# CAP_Group.net
KiCad netlist of a schematic drawn in Altium Designer
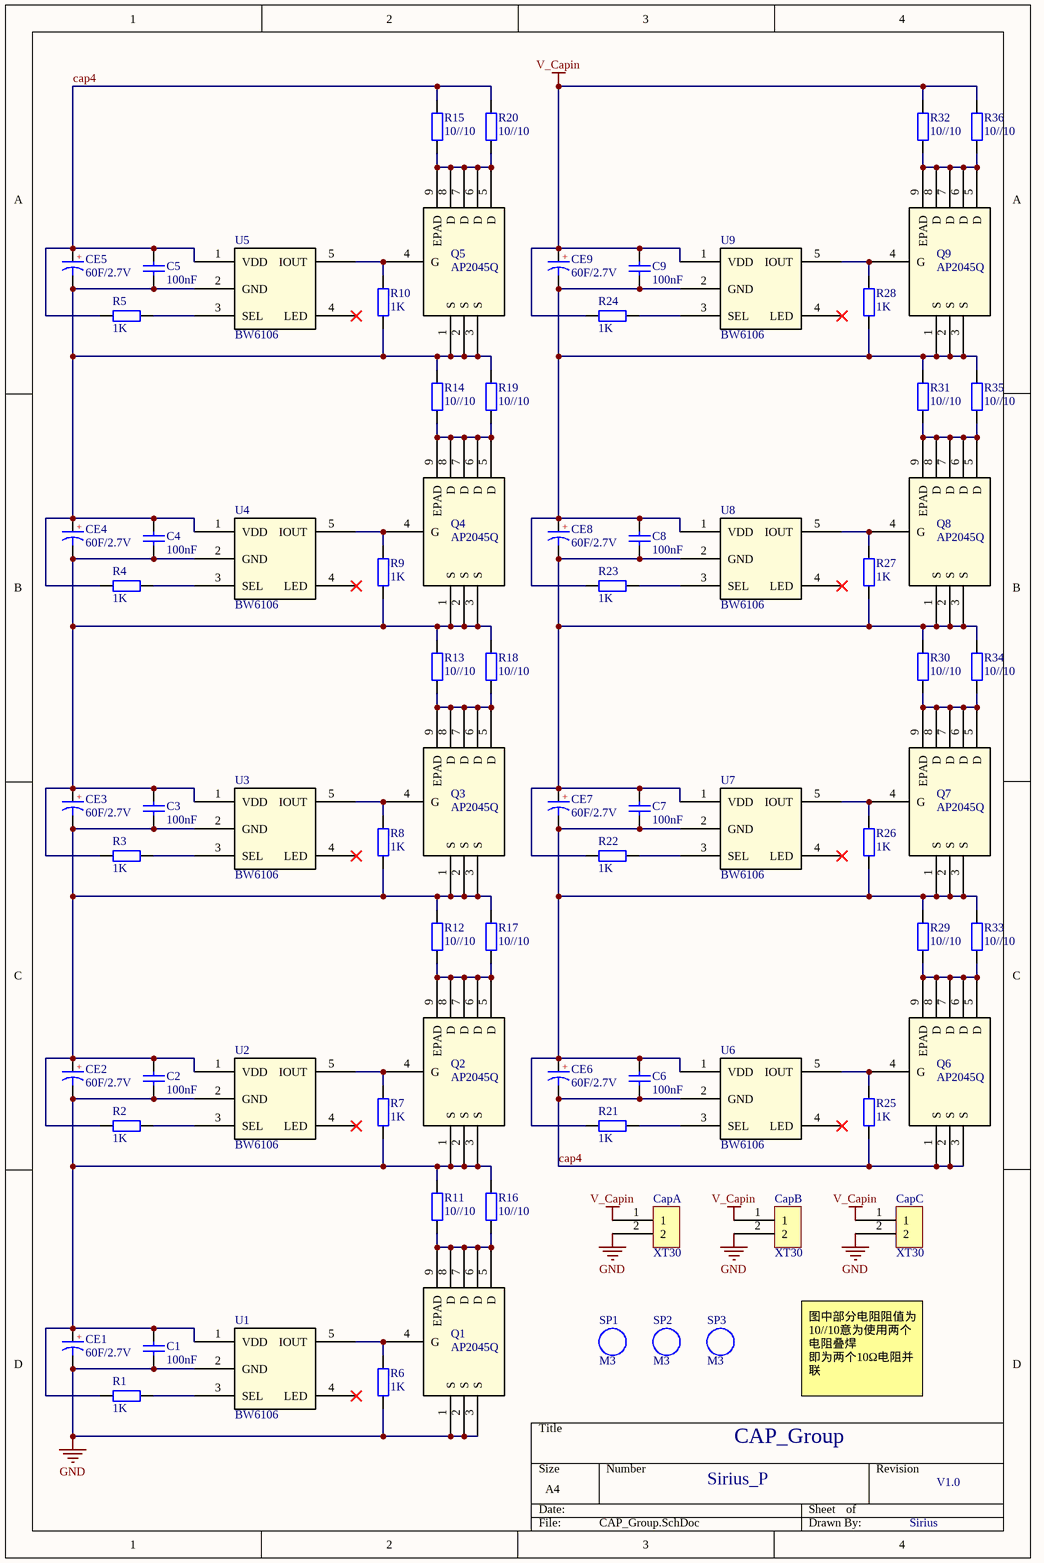
[diagram p0: CAP_Group.SchDoc]

(export (version "E")
  (design (tool "Eeschema 10.0.6"))
  (components
    (comp (ref "C1")
      (value "100nF")
      (footprint "C0603_L")
      (description "贴片电容")
      (libsource (lib "0.1 - 电阻-电容-电感-晶振-晶体-磁珠-电位器") (part "C"))
    )
    (comp (ref "C2")
      (value "100nF")
      (footprint "C0603_L")
      (description "贴片电容")
      (libsource (lib "0.1 - 电阻-电容-电感-晶振-晶体-磁珠-电位器") (part "C"))
    )
    (comp (ref "C3")
      (value "100nF")
      (footprint "C0603_L")
      (description "贴片电容")
      (libsource (lib "0.1 - 电阻-电容-电感-晶振-晶体-磁珠-电位器") (part "C"))
    )
    (comp (ref "C4")
      (value "100nF")
      (footprint "C0603_L")
      (description "贴片电容")
      (libsource (lib "0.1 - 电阻-电容-电感-晶振-晶体-磁珠-电位器") (part "C"))
    )
    (comp (ref "C5")
      (value "100nF")
      (footprint "C0603_L")
      (description "贴片电容")
      (libsource (lib "0.1 - 电阻-电容-电感-晶振-晶体-磁珠-电位器") (part "C"))
    )
    (comp (ref "C6")
      (value "100nF")
      (footprint "C0603_L")
      (description "贴片电容")
      (libsource (lib "0.1 - 电阻-电容-电感-晶振-晶体-磁珠-电位器") (part "C"))
    )
    (comp (ref "C7")
      (value "100nF")
      (footprint "C0603_L")
      (description "贴片电容")
      (libsource (lib "0.1 - 电阻-电容-电感-晶振-晶体-磁珠-电位器") (part "C"))
    )
    (comp (ref "C8")
      (value "100nF")
      (footprint "C0603_L")
      (description "贴片电容")
      (libsource (lib "0.1 - 电阻-电容-电感-晶振-晶体-磁珠-电位器") (part "C"))
    )
    (comp (ref "C9")
      (value "100nF")
      (footprint "C0603_L")
      (description "贴片电容")
      (libsource (lib "0.1 - 电阻-电容-电感-晶振-晶体-磁珠-电位器") (part "C"))
    )
    (comp (ref "CapA") (value "XT30") (footprint "XT30-F") (libsource (lib "Extra Sch") (part "XT30")))
    (comp (ref "CapB") (value "XT30") (footprint "XT30-F") (libsource (lib "Extra Sch") (part "XT30")))
    (comp (ref "CapC") (value "XT30") (footprint "XT30-F") (libsource (lib "Extra Sch") (part "XT30")))
    (comp (ref "CE1")
      (value "60F/2.7V")
      (footprint "CE-7.5*18*35.5 - BK")
      (description "直插电解电容")
      (libsource (lib "0.1 - 电阻-电容-电感-晶振-晶体-磁珠-电位器") (part "CE"))
    )
    (comp (ref "CE2")
      (value "60F/2.7V")
      (footprint "CE-7.5*18*35.5 - BK")
      (description "直插电解电容")
      (libsource (lib "0.1 - 电阻-电容-电感-晶振-晶体-磁珠-电位器") (part "CE"))
    )
    (comp (ref "CE3")
      (value "60F/2.7V")
      (footprint "CE-7.5*18*35.5 - BK")
      (description "直插电解电容")
      (libsource (lib "0.1 - 电阻-电容-电感-晶振-晶体-磁珠-电位器") (part "CE"))
    )
    (comp (ref "CE4")
      (value "60F/2.7V")
      (footprint "CE-7.5*18*35.5 - BK")
      (description "直插电解电容")
      (libsource (lib "0.1 - 电阻-电容-电感-晶振-晶体-磁珠-电位器") (part "CE"))
    )
    (comp (ref "CE5")
      (value "60F/2.7V")
      (footprint "CE-7.5*18*35.5 - BK")
      (description "直插电解电容")
      (libsource (lib "0.1 - 电阻-电容-电感-晶振-晶体-磁珠-电位器") (part "CE"))
    )
    (comp (ref "CE6")
      (value "60F/2.7V")
      (footprint "CE-7.5*18*35.5 - BK")
      (description "直插电解电容")
      (libsource (lib "0.1 - 电阻-电容-电感-晶振-晶体-磁珠-电位器") (part "CE"))
    )
    (comp (ref "CE7")
      (value "60F/2.7V")
      (footprint "CE-7.5*18*35.5 - BK")
      (description "直插电解电容")
      (libsource (lib "0.1 - 电阻-电容-电感-晶振-晶体-磁珠-电位器") (part "CE"))
    )
    (comp (ref "CE8")
      (value "60F/2.7V")
      (footprint "CE-7.5*18*35.5 - BK")
      (description "直插电解电容")
      (libsource (lib "0.1 - 电阻-电容-电感-晶振-晶体-磁珠-电位器") (part "CE"))
    )
    (comp (ref "CE9")
      (value "60F/2.7V")
      (footprint "CE-7.5*18*35.5 - BK")
      (description "直插电解电容")
      (libsource (lib "0.1 - 电阻-电容-电感-晶振-晶体-磁珠-电位器") (part "CE"))
    )
    (comp (ref "Q1")
      (value "AP2045Q")
      (footprint "TDFN33-8")
      (description "Trans MOSFET P-CH 20V 65A 8-Pin PDFN EP T/R")
      (fields
        (field (name "MANUFACTURER_PART_NUMBER") "TSM085P03CV RGG")
        (field (name "MOUSER PART NUMBER") "821-TSM085P03CVRGG")
      )
      (libsource (lib "Extra Sch") (part "AP2045Q"))
    )
    (comp (ref "Q2")
      (value "AP2045Q")
      (footprint "TDFN33-8")
      (description "Trans MOSFET P-CH 20V 65A 8-Pin PDFN EP T/R")
      (fields
        (field (name "MANUFACTURER_PART_NUMBER") "TSM085P03CV RGG")
        (field (name "MOUSER PART NUMBER") "821-TSM085P03CVRGG")
      )
      (libsource (lib "Extra Sch") (part "AP2045Q"))
    )
    (comp (ref "Q3")
      (value "AP2045Q")
      (footprint "TDFN33-8")
      (description "Trans MOSFET P-CH 20V 65A 8-Pin PDFN EP T/R")
      (fields
        (field (name "MANUFACTURER_PART_NUMBER") "TSM085P03CV RGG")
        (field (name "MOUSER PART NUMBER") "821-TSM085P03CVRGG")
      )
      (libsource (lib "Extra Sch") (part "AP2045Q"))
    )
    (comp (ref "Q4")
      (value "AP2045Q")
      (footprint "TDFN33-8")
      (description "Trans MOSFET P-CH 20V 65A 8-Pin PDFN EP T/R")
      (fields
        (field (name "MANUFACTURER_PART_NUMBER") "TSM085P03CV RGG")
        (field (name "MOUSER PART NUMBER") "821-TSM085P03CVRGG")
      )
      (libsource (lib "Extra Sch") (part "AP2045Q"))
    )
    (comp (ref "Q5")
      (value "AP2045Q")
      (footprint "TDFN33-8")
      (description "Trans MOSFET P-CH 20V 65A 8-Pin PDFN EP T/R")
      (fields
        (field (name "MANUFACTURER_PART_NUMBER") "TSM085P03CV RGG")
        (field (name "MOUSER PART NUMBER") "821-TSM085P03CVRGG")
      )
      (libsource (lib "Extra Sch") (part "AP2045Q"))
    )
    (comp (ref "Q6")
      (value "AP2045Q")
      (footprint "TDFN33-8")
      (description "Trans MOSFET P-CH 20V 65A 8-Pin PDFN EP T/R")
      (fields
        (field (name "MANUFACTURER_PART_NUMBER") "TSM085P03CV RGG")
        (field (name "MOUSER PART NUMBER") "821-TSM085P03CVRGG")
      )
      (libsource (lib "Extra Sch") (part "AP2045Q"))
    )
    (comp (ref "Q7")
      (value "AP2045Q")
      (footprint "TDFN33-8")
      (description "Trans MOSFET P-CH 20V 65A 8-Pin PDFN EP T/R")
      (fields
        (field (name "MANUFACTURER_PART_NUMBER") "TSM085P03CV RGG")
        (field (name "MOUSER PART NUMBER") "821-TSM085P03CVRGG")
      )
      (libsource (lib "Extra Sch") (part "AP2045Q"))
    )
    (comp (ref "Q8")
      (value "AP2045Q")
      (footprint "TDFN33-8")
      (description "Trans MOSFET P-CH 20V 65A 8-Pin PDFN EP T/R")
      (fields
        (field (name "MANUFACTURER_PART_NUMBER") "TSM085P03CV RGG")
        (field (name "MOUSER PART NUMBER") "821-TSM085P03CVRGG")
      )
      (libsource (lib "Extra Sch") (part "AP2045Q"))
    )
    (comp (ref "Q9")
      (value "AP2045Q")
      (footprint "TDFN33-8")
      (description "Trans MOSFET P-CH 20V 65A 8-Pin PDFN EP T/R")
      (fields
        (field (name "MANUFACTURER_PART_NUMBER") "TSM085P03CV RGG")
        (field (name "MOUSER PART NUMBER") "821-TSM085P03CVRGG")
      )
      (libsource (lib "Extra Sch") (part "AP2045Q"))
    )
    (comp (ref "R1")
      (value "1K")
      (footprint "R0603_L")
      (description "贴片电阻")
      (libsource (lib "0.1 - 电阻-电容-电感-晶振-晶体-磁珠-电位器") (part "R"))
    )
    (comp (ref "R2")
      (value "1K")
      (footprint "R0603_L")
      (description "贴片电阻")
      (libsource (lib "0.1 - 电阻-电容-电感-晶振-晶体-磁珠-电位器") (part "R"))
    )
    (comp (ref "R3")
      (value "1K")
      (footprint "R0603_L")
      (description "贴片电阻")
      (libsource (lib "0.1 - 电阻-电容-电感-晶振-晶体-磁珠-电位器") (part "R"))
    )
    (comp (ref "R4")
      (value "1K")
      (footprint "R0603_L")
      (description "贴片电阻")
      (libsource (lib "0.1 - 电阻-电容-电感-晶振-晶体-磁珠-电位器") (part "R"))
    )
    (comp (ref "R5")
      (value "1K")
      (footprint "R0603_L")
      (description "贴片电阻")
      (libsource (lib "0.1 - 电阻-电容-电感-晶振-晶体-磁珠-电位器") (part "R"))
    )
    (comp (ref "R6")
      (value "1K")
      (footprint "R0603_L")
      (description "贴片电阻")
      (libsource (lib "0.1 - 电阻-电容-电感-晶振-晶体-磁珠-电位器") (part "R"))
    )
    (comp (ref "R7")
      (value "1K")
      (footprint "R0603_L")
      (description "贴片电阻")
      (libsource (lib "0.1 - 电阻-电容-电感-晶振-晶体-磁珠-电位器") (part "R"))
    )
    (comp (ref "R8")
      (value "1K")
      (footprint "R0603_L")
      (description "贴片电阻")
      (libsource (lib "0.1 - 电阻-电容-电感-晶振-晶体-磁珠-电位器") (part "R"))
    )
    (comp (ref "R9")
      (value "1K")
      (footprint "R0603_L")
      (description "贴片电阻")
      (libsource (lib "0.1 - 电阻-电容-电感-晶振-晶体-磁珠-电位器") (part "R"))
    )
    (comp (ref "R10")
      (value "1K")
      (footprint "R0603_L")
      (description "贴片电阻")
      (libsource (lib "0.1 - 电阻-电容-电感-晶振-晶体-磁珠-电位器") (part "R"))
    )
    (comp (ref "R11")
      (value "10//10")
      (footprint "R2512_L")
      (description "贴片电阻")
      (libsource (lib "0.1 - 电阻-电容-电感-晶振-晶体-磁珠-电位器") (part "R"))
    )
    (comp (ref "R12")
      (value "10//10")
      (footprint "R2512_L")
      (description "贴片电阻")
      (libsource (lib "0.1 - 电阻-电容-电感-晶振-晶体-磁珠-电位器") (part "R"))
    )
    (comp (ref "R13")
      (value "10//10")
      (footprint "R2512_L")
      (description "贴片电阻")
      (libsource (lib "0.1 - 电阻-电容-电感-晶振-晶体-磁珠-电位器") (part "R"))
    )
    (comp (ref "R14")
      (value "10//10")
      (footprint "R2512_L")
      (description "贴片电阻")
      (libsource (lib "0.1 - 电阻-电容-电感-晶振-晶体-磁珠-电位器") (part "R"))
    )
    (comp (ref "R15")
      (value "10//10")
      (footprint "R2512_L")
      (description "贴片电阻")
      (libsource (lib "0.1 - 电阻-电容-电感-晶振-晶体-磁珠-电位器") (part "R"))
    )
    (comp (ref "R16")
      (value "10//10")
      (footprint "R2512_L")
      (description "贴片电阻")
      (libsource (lib "0.1 - 电阻-电容-电感-晶振-晶体-磁珠-电位器") (part "R"))
    )
    (comp (ref "R17")
      (value "10//10")
      (footprint "R2512_L")
      (description "贴片电阻")
      (libsource (lib "0.1 - 电阻-电容-电感-晶振-晶体-磁珠-电位器") (part "R"))
    )
    (comp (ref "R18")
      (value "10//10")
      (footprint "R2512_L")
      (description "贴片电阻")
      (libsource (lib "0.1 - 电阻-电容-电感-晶振-晶体-磁珠-电位器") (part "R"))
    )
    (comp (ref "R19")
      (value "10//10")
      (footprint "R2512_L")
      (description "贴片电阻")
      (libsource (lib "0.1 - 电阻-电容-电感-晶振-晶体-磁珠-电位器") (part "R"))
    )
    (comp (ref "R20")
      (value "10//10")
      (footprint "R2512_L")
      (description "贴片电阻")
      (libsource (lib "0.1 - 电阻-电容-电感-晶振-晶体-磁珠-电位器") (part "R"))
    )
    (comp (ref "R21")
      (value "1K")
      (footprint "R0603_L")
      (description "贴片电阻")
      (libsource (lib "0.1 - 电阻-电容-电感-晶振-晶体-磁珠-电位器") (part "R"))
    )
    (comp (ref "R22")
      (value "1K")
      (footprint "R0603_L")
      (description "贴片电阻")
      (libsource (lib "0.1 - 电阻-电容-电感-晶振-晶体-磁珠-电位器") (part "R"))
    )
    (comp (ref "R23")
      (value "1K")
      (footprint "R0603_L")
      (description "贴片电阻")
      (libsource (lib "0.1 - 电阻-电容-电感-晶振-晶体-磁珠-电位器") (part "R"))
    )
    (comp (ref "R24")
      (value "1K")
      (footprint "R0603_L")
      (description "贴片电阻")
      (libsource (lib "0.1 - 电阻-电容-电感-晶振-晶体-磁珠-电位器") (part "R"))
    )
    (comp (ref "R25")
      (value "1K")
      (footprint "R0603_L")
      (description "贴片电阻")
      (libsource (lib "0.1 - 电阻-电容-电感-晶振-晶体-磁珠-电位器") (part "R"))
    )
    (comp (ref "R26")
      (value "1K")
      (footprint "R0603_L")
      (description "贴片电阻")
      (libsource (lib "0.1 - 电阻-电容-电感-晶振-晶体-磁珠-电位器") (part "R"))
    )
    (comp (ref "R27")
      (value "1K")
      (footprint "R0603_L")
      (description "贴片电阻")
      (libsource (lib "0.1 - 电阻-电容-电感-晶振-晶体-磁珠-电位器") (part "R"))
    )
    (comp (ref "R28")
      (value "1K")
      (footprint "R0603_L")
      (description "贴片电阻")
      (libsource (lib "0.1 - 电阻-电容-电感-晶振-晶体-磁珠-电位器") (part "R"))
    )
    (comp (ref "R29")
      (value "10//10")
      (footprint "R2512_L")
      (description "贴片电阻")
      (libsource (lib "0.1 - 电阻-电容-电感-晶振-晶体-磁珠-电位器") (part "R"))
    )
    (comp (ref "R30")
      (value "10//10")
      (footprint "R2512_L")
      (description "贴片电阻")
      (libsource (lib "0.1 - 电阻-电容-电感-晶振-晶体-磁珠-电位器") (part "R"))
    )
    (comp (ref "R31")
      (value "10//10")
      (footprint "R2512_L")
      (description "贴片电阻")
      (libsource (lib "0.1 - 电阻-电容-电感-晶振-晶体-磁珠-电位器") (part "R"))
    )
    (comp (ref "R32")
      (value "10//10")
      (footprint "R2512_L")
      (description "贴片电阻")
      (libsource (lib "0.1 - 电阻-电容-电感-晶振-晶体-磁珠-电位器") (part "R"))
    )
    (comp (ref "R33")
      (value "10//10")
      (footprint "R2512_L")
      (description "贴片电阻")
      (libsource (lib "0.1 - 电阻-电容-电感-晶振-晶体-磁珠-电位器") (part "R"))
    )
    (comp (ref "R34")
      (value "10//10")
      (footprint "R2512_L")
      (description "贴片电阻")
      (libsource (lib "0.1 - 电阻-电容-电感-晶振-晶体-磁珠-电位器") (part "R"))
    )
    (comp (ref "R35")
      (value "10//10")
      (footprint "R2512_L")
      (description "贴片电阻")
      (libsource (lib "0.1 - 电阻-电容-电感-晶振-晶体-磁珠-电位器") (part "R"))
    )
    (comp (ref "R36")
      (value "10//10")
      (footprint "R2512_L")
      (description "贴片电阻")
      (libsource (lib "0.1 - 电阻-电容-电感-晶振-晶体-磁珠-电位器") (part "R"))
    )
    (comp (ref "SP1")
      (value "M3")
      (footprint "M3 125X200")
      (description "铜柱孔")
      (libsource (lib "0.5 - 按键-开关-蜂鸣器-保险丝-电池-测试点-Mark点") (part "M3"))
    )
    (comp (ref "SP2")
      (value "M3")
      (footprint "M3 125X200")
      (description "铜柱孔")
      (libsource (lib "0.5 - 按键-开关-蜂鸣器-保险丝-电池-测试点-Mark点") (part "M3"))
    )
    (comp (ref "SP3")
      (value "M3")
      (footprint "M3 125X200")
      (description "铜柱孔")
      (libsource (lib "0.5 - 按键-开关-蜂鸣器-保险丝-电池-测试点-Mark点") (part "M3"))
    )
    (comp (ref "U1")
      (value "BW6106")
      (footprint "SOT23-5L")
      (description "电容充电保护芯片")
      (libsource (lib "Extra Sch") (part "BW6106"))
    )
    (comp (ref "U2")
      (value "BW6106")
      (footprint "SOT23-5L")
      (description "电容充电保护芯片")
      (libsource (lib "Extra Sch") (part "BW6106"))
    )
    (comp (ref "U3")
      (value "BW6106")
      (footprint "SOT23-5L")
      (description "电容充电保护芯片")
      (libsource (lib "Extra Sch") (part "BW6106"))
    )
    (comp (ref "U4")
      (value "BW6106")
      (footprint "SOT23-5L")
      (description "电容充电保护芯片")
      (libsource (lib "Extra Sch") (part "BW6106"))
    )
    (comp (ref "U5")
      (value "BW6106")
      (footprint "SOT23-5L")
      (description "电容充电保护芯片")
      (libsource (lib "Extra Sch") (part "BW6106"))
    )
    (comp (ref "U6")
      (value "BW6106")
      (footprint "SOT23-5L")
      (description "电容充电保护芯片")
      (libsource (lib "Extra Sch") (part "BW6106"))
    )
    (comp (ref "U7")
      (value "BW6106")
      (footprint "SOT23-5L")
      (description "电容充电保护芯片")
      (libsource (lib "Extra Sch") (part "BW6106"))
    )
    (comp (ref "U8")
      (value "BW6106")
      (footprint "SOT23-5L")
      (description "电容充电保护芯片")
      (libsource (lib "Extra Sch") (part "BW6106"))
    )
    (comp (ref "U9")
      (value "BW6106")
      (footprint "SOT23-5L")
      (description "电容充电保护芯片")
      (libsource (lib "Extra Sch") (part "BW6106"))
    )
  )
  (nets
    (net (code "1") (name "/cap4") (class "Default")
      (node (ref "C5") (pin "1") (pinfunction "1_1") (pintype "passive"))
      (node (ref "C6") (pin "2") (pinfunction "2_2") (pintype "passive"))
      (node (ref "CE5") (pin "1") (pinfunction "1_1") (pintype "passive"))
      (node (ref "CE6") (pin "2") (pinfunction "2_2") (pintype "passive"))
      (node (ref "Q6") (pin "1") (pinfunction "S_1") (pintype "passive"))
      (node (ref "Q6") (pin "2") (pinfunction "S_2") (pintype "passive"))
      (node (ref "Q6") (pin "3") (pinfunction "S_3") (pintype "passive"))
      (node (ref "R15") (pin "2") (pinfunction "2_2") (pintype "passive"))
      (node (ref "R20") (pin "2") (pinfunction "2_2") (pintype "passive"))
      (node (ref "R25") (pin "1") (pinfunction "1_1") (pintype "passive"))
      (node (ref "R5") (pin "1") (pinfunction "1_1") (pintype "passive"))
      (node (ref "U5") (pin "1") (pinfunction "VDD_1") (pintype "passive"))
      (node (ref "U6") (pin "2") (pinfunction "GND_2") (pintype "passive"))
    )
    (net (code "2") (name "GND") (class "Default")
      (node (ref "C1") (pin "2") (pinfunction "2_2") (pintype "passive"))
      (node (ref "CE1") (pin "2") (pinfunction "2_2") (pintype "passive"))
      (node (ref "CapA") (pin "2") (pinfunction "2_2") (pintype "passive"))
      (node (ref "CapB") (pin "2") (pinfunction "2_2") (pintype "passive"))
      (node (ref "CapC") (pin "2") (pinfunction "2_2") (pintype "passive"))
      (node (ref "Q1") (pin "1") (pinfunction "S_1") (pintype "passive"))
      (node (ref "Q1") (pin "2") (pinfunction "S_2") (pintype "passive"))
      (node (ref "Q1") (pin "3") (pinfunction "S_3") (pintype "passive"))
      (node (ref "R6") (pin "1") (pinfunction "1_1") (pintype "passive"))
      (node (ref "U1") (pin "2") (pinfunction "GND_2") (pintype "passive"))
    )
    (net (code "3") (name "Net-(Q1-EPAD)") (class "Default")
      (node (ref "Q1") (pin "5") (pinfunction "D_5") (pintype "passive"))
      (node (ref "Q1") (pin "6") (pinfunction "D_6") (pintype "passive"))
      (node (ref "Q1") (pin "7") (pinfunction "D_7") (pintype "passive"))
      (node (ref "Q1") (pin "8") (pinfunction "D_8") (pintype "passive"))
      (node (ref "Q1") (pin "9") (pinfunction "EPAD_9") (pintype "passive"))
      (node (ref "R11") (pin "1") (pinfunction "1_1") (pintype "passive"))
      (node (ref "R16") (pin "1") (pinfunction "1_1") (pintype "passive"))
    )
    (net (code "4") (name "Net-(Q1-G)") (class "Default")
      (node (ref "Q1") (pin "4") (pinfunction "G_4") (pintype "passive"))
      (node (ref "R6") (pin "2") (pinfunction "2_2") (pintype "passive"))
      (node (ref "U1") (pin "5") (pinfunction "IOUT_5") (pintype "passive"))
    )
    (net (code "5") (name "Net-(Q2-EPAD)") (class "Default")
      (node (ref "Q2") (pin "5") (pinfunction "D_5") (pintype "passive"))
      (node (ref "Q2") (pin "6") (pinfunction "D_6") (pintype "passive"))
      (node (ref "Q2") (pin "7") (pinfunction "D_7") (pintype "passive"))
      (node (ref "Q2") (pin "8") (pinfunction "D_8") (pintype "passive"))
      (node (ref "Q2") (pin "9") (pinfunction "EPAD_9") (pintype "passive"))
      (node (ref "R12") (pin "1") (pinfunction "1_1") (pintype "passive"))
      (node (ref "R17") (pin "1") (pinfunction "1_1") (pintype "passive"))
    )
    (net (code "6") (name "Net-(Q2-G)") (class "Default")
      (node (ref "Q2") (pin "4") (pinfunction "G_4") (pintype "passive"))
      (node (ref "R7") (pin "2") (pinfunction "2_2") (pintype "passive"))
      (node (ref "U2") (pin "5") (pinfunction "IOUT_5") (pintype "passive"))
    )
    (net (code "7") (name "Net-(Q3-EPAD)") (class "Default")
      (node (ref "Q3") (pin "5") (pinfunction "D_5") (pintype "passive"))
      (node (ref "Q3") (pin "6") (pinfunction "D_6") (pintype "passive"))
      (node (ref "Q3") (pin "7") (pinfunction "D_7") (pintype "passive"))
      (node (ref "Q3") (pin "8") (pinfunction "D_8") (pintype "passive"))
      (node (ref "Q3") (pin "9") (pinfunction "EPAD_9") (pintype "passive"))
      (node (ref "R13") (pin "1") (pinfunction "1_1") (pintype "passive"))
      (node (ref "R18") (pin "1") (pinfunction "1_1") (pintype "passive"))
    )
    (net (code "8") (name "Net-(Q3-G)") (class "Default")
      (node (ref "Q3") (pin "4") (pinfunction "G_4") (pintype "passive"))
      (node (ref "R8") (pin "2") (pinfunction "2_2") (pintype "passive"))
      (node (ref "U3") (pin "5") (pinfunction "IOUT_5") (pintype "passive"))
    )
    (net (code "9") (name "Net-(Q4-EPAD)") (class "Default")
      (node (ref "Q4") (pin "5") (pinfunction "D_5") (pintype "passive"))
      (node (ref "Q4") (pin "6") (pinfunction "D_6") (pintype "passive"))
      (node (ref "Q4") (pin "7") (pinfunction "D_7") (pintype "passive"))
      (node (ref "Q4") (pin "8") (pinfunction "D_8") (pintype "passive"))
      (node (ref "Q4") (pin "9") (pinfunction "EPAD_9") (pintype "passive"))
      (node (ref "R14") (pin "1") (pinfunction "1_1") (pintype "passive"))
      (node (ref "R19") (pin "1") (pinfunction "1_1") (pintype "passive"))
    )
    (net (code "10") (name "Net-(Q4-G)") (class "Default")
      (node (ref "Q4") (pin "4") (pinfunction "G_4") (pintype "passive"))
      (node (ref "R9") (pin "2") (pinfunction "2_2") (pintype "passive"))
      (node (ref "U4") (pin "5") (pinfunction "IOUT_5") (pintype "passive"))
    )
    (net (code "11") (name "Net-(Q5-EPAD)") (class "Default")
      (node (ref "Q5") (pin "5") (pinfunction "D_5") (pintype "passive"))
      (node (ref "Q5") (pin "6") (pinfunction "D_6") (pintype "passive"))
      (node (ref "Q5") (pin "7") (pinfunction "D_7") (pintype "passive"))
      (node (ref "Q5") (pin "8") (pinfunction "D_8") (pintype "passive"))
      (node (ref "Q5") (pin "9") (pinfunction "EPAD_9") (pintype "passive"))
      (node (ref "R15") (pin "1") (pinfunction "1_1") (pintype "passive"))
      (node (ref "R20") (pin "1") (pinfunction "1_1") (pintype "passive"))
    )
    (net (code "12") (name "Net-(Q5-G)") (class "Default")
      (node (ref "Q5") (pin "4") (pinfunction "G_4") (pintype "passive"))
      (node (ref "R10") (pin "2") (pinfunction "2_2") (pintype "passive"))
      (node (ref "U5") (pin "5") (pinfunction "IOUT_5") (pintype "passive"))
    )
    (net (code "13") (name "Net-(Q6-EPAD)") (class "Default")
      (node (ref "Q6") (pin "5") (pinfunction "D_5") (pintype "passive"))
      (node (ref "Q6") (pin "6") (pinfunction "D_6") (pintype "passive"))
      (node (ref "Q6") (pin "7") (pinfunction "D_7") (pintype "passive"))
      (node (ref "Q6") (pin "8") (pinfunction "D_8") (pintype "passive"))
      (node (ref "Q6") (pin "9") (pinfunction "EPAD_9") (pintype "passive"))
      (node (ref "R29") (pin "1") (pinfunction "1_1") (pintype "passive"))
      (node (ref "R33") (pin "1") (pinfunction "1_1") (pintype "passive"))
    )
    (net (code "14") (name "Net-(Q6-G)") (class "Default")
      (node (ref "Q6") (pin "4") (pinfunction "G_4") (pintype "passive"))
      (node (ref "R25") (pin "2") (pinfunction "2_2") (pintype "passive"))
      (node (ref "U6") (pin "5") (pinfunction "IOUT_5") (pintype "passive"))
    )
    (net (code "15") (name "Net-(Q7-EPAD)") (class "Default")
      (node (ref "Q7") (pin "5") (pinfunction "D_5") (pintype "passive"))
      (node (ref "Q7") (pin "6") (pinfunction "D_6") (pintype "passive"))
      (node (ref "Q7") (pin "7") (pinfunction "D_7") (pintype "passive"))
      (node (ref "Q7") (pin "8") (pinfunction "D_8") (pintype "passive"))
      (node (ref "Q7") (pin "9") (pinfunction "EPAD_9") (pintype "passive"))
      (node (ref "R30") (pin "1") (pinfunction "1_1") (pintype "passive"))
      (node (ref "R34") (pin "1") (pinfunction "1_1") (pintype "passive"))
    )
    (net (code "16") (name "Net-(Q7-G)") (class "Default")
      (node (ref "Q7") (pin "4") (pinfunction "G_4") (pintype "passive"))
      (node (ref "R26") (pin "2") (pinfunction "2_2") (pintype "passive"))
      (node (ref "U7") (pin "5") (pinfunction "IOUT_5") (pintype "passive"))
    )
    (net (code "17") (name "Net-(Q8-EPAD)") (class "Default")
      (node (ref "Q8") (pin "5") (pinfunction "D_5") (pintype "passive"))
      (node (ref "Q8") (pin "6") (pinfunction "D_6") (pintype "passive"))
      (node (ref "Q8") (pin "7") (pinfunction "D_7") (pintype "passive"))
      (node (ref "Q8") (pin "8") (pinfunction "D_8") (pintype "passive"))
      (node (ref "Q8") (pin "9") (pinfunction "EPAD_9") (pintype "passive"))
      (node (ref "R31") (pin "1") (pinfunction "1_1") (pintype "passive"))
      (node (ref "R35") (pin "1") (pinfunction "1_1") (pintype "passive"))
    )
    (net (code "18") (name "Net-(Q8-G)") (class "Default")
      (node (ref "Q8") (pin "4") (pinfunction "G_4") (pintype "passive"))
      (node (ref "R27") (pin "2") (pinfunction "2_2") (pintype "passive"))
      (node (ref "U8") (pin "5") (pinfunction "IOUT_5") (pintype "passive"))
    )
    (net (code "19") (name "Net-(Q9-EPAD)") (class "Default")
      (node (ref "Q9") (pin "5") (pinfunction "D_5") (pintype "passive"))
      (node (ref "Q9") (pin "6") (pinfunction "D_6") (pintype "passive"))
      (node (ref "Q9") (pin "7") (pinfunction "D_7") (pintype "passive"))
      (node (ref "Q9") (pin "8") (pinfunction "D_8") (pintype "passive"))
      (node (ref "Q9") (pin "9") (pinfunction "EPAD_9") (pintype "passive"))
      (node (ref "R32") (pin "1") (pinfunction "1_1") (pintype "passive"))
      (node (ref "R36") (pin "1") (pinfunction "1_1") (pintype "passive"))
    )
    (net (code "20") (name "Net-(Q9-G)") (class "Default")
      (node (ref "Q9") (pin "4") (pinfunction "G_4") (pintype "passive"))
      (node (ref "R28") (pin "2") (pinfunction "2_2") (pintype "passive"))
      (node (ref "U9") (pin "5") (pinfunction "IOUT_5") (pintype "passive"))
    )
    (net (code "21") (name "Net-(U1-SEL)") (class "Default")
      (node (ref "R1") (pin "2") (pinfunction "2_2") (pintype "passive"))
      (node (ref "U1") (pin "3") (pinfunction "SEL_3") (pintype "passive"))
    )
    (net (code "22") (name "Net-(U1-VDD)") (class "Default")
      (node (ref "C1") (pin "1") (pinfunction "1_1") (pintype "passive"))
      (node (ref "C2") (pin "2") (pinfunction "2_2") (pintype "passive"))
      (node (ref "CE1") (pin "1") (pinfunction "1_1") (pintype "passive"))
      (node (ref "CE2") (pin "2") (pinfunction "2_2") (pintype "passive"))
      (node (ref "Q2") (pin "1") (pinfunction "S_1") (pintype "passive"))
      (node (ref "Q2") (pin "2") (pinfunction "S_2") (pintype "passive"))
      (node (ref "Q2") (pin "3") (pinfunction "S_3") (pintype "passive"))
      (node (ref "R1") (pin "1") (pinfunction "1_1") (pintype "passive"))
      (node (ref "R11") (pin "2") (pinfunction "2_2") (pintype "passive"))
      (node (ref "R16") (pin "2") (pinfunction "2_2") (pintype "passive"))
      (node (ref "R7") (pin "1") (pinfunction "1_1") (pintype "passive"))
      (node (ref "U1") (pin "1") (pinfunction "VDD_1") (pintype "passive"))
      (node (ref "U2") (pin "2") (pinfunction "GND_2") (pintype "passive"))
    )
    (net (code "23") (name "Net-(U2-SEL)") (class "Default")
      (node (ref "R2") (pin "2") (pinfunction "2_2") (pintype "passive"))
      (node (ref "U2") (pin "3") (pinfunction "SEL_3") (pintype "passive"))
    )
    (net (code "24") (name "Net-(U2-VDD)") (class "Default")
      (node (ref "C2") (pin "1") (pinfunction "1_1") (pintype "passive"))
      (node (ref "C3") (pin "2") (pinfunction "2_2") (pintype "passive"))
      (node (ref "CE2") (pin "1") (pinfunction "1_1") (pintype "passive"))
      (node (ref "CE3") (pin "2") (pinfunction "2_2") (pintype "passive"))
      (node (ref "Q3") (pin "1") (pinfunction "S_1") (pintype "passive"))
      (node (ref "Q3") (pin "2") (pinfunction "S_2") (pintype "passive"))
      (node (ref "Q3") (pin "3") (pinfunction "S_3") (pintype "passive"))
      (node (ref "R12") (pin "2") (pinfunction "2_2") (pintype "passive"))
      (node (ref "R17") (pin "2") (pinfunction "2_2") (pintype "passive"))
      (node (ref "R2") (pin "1") (pinfunction "1_1") (pintype "passive"))
      (node (ref "R8") (pin "1") (pinfunction "1_1") (pintype "passive"))
      (node (ref "U2") (pin "1") (pinfunction "VDD_1") (pintype "passive"))
      (node (ref "U3") (pin "2") (pinfunction "GND_2") (pintype "passive"))
    )
    (net (code "25") (name "Net-(U3-SEL)") (class "Default")
      (node (ref "R3") (pin "2") (pinfunction "2_2") (pintype "passive"))
      (node (ref "U3") (pin "3") (pinfunction "SEL_3") (pintype "passive"))
    )
    (net (code "26") (name "Net-(U3-VDD)") (class "Default")
      (node (ref "C3") (pin "1") (pinfunction "1_1") (pintype "passive"))
      (node (ref "C4") (pin "2") (pinfunction "2_2") (pintype "passive"))
      (node (ref "CE3") (pin "1") (pinfunction "1_1") (pintype "passive"))
      (node (ref "CE4") (pin "2") (pinfunction "2_2") (pintype "passive"))
      (node (ref "Q4") (pin "1") (pinfunction "S_1") (pintype "passive"))
      (node (ref "Q4") (pin "2") (pinfunction "S_2") (pintype "passive"))
      (node (ref "Q4") (pin "3") (pinfunction "S_3") (pintype "passive"))
      (node (ref "R13") (pin "2") (pinfunction "2_2") (pintype "passive"))
      (node (ref "R18") (pin "2") (pinfunction "2_2") (pintype "passive"))
      (node (ref "R3") (pin "1") (pinfunction "1_1") (pintype "passive"))
      (node (ref "R9") (pin "1") (pinfunction "1_1") (pintype "passive"))
      (node (ref "U3") (pin "1") (pinfunction "VDD_1") (pintype "passive"))
      (node (ref "U4") (pin "2") (pinfunction "GND_2") (pintype "passive"))
    )
    (net (code "27") (name "Net-(U4-SEL)") (class "Default")
      (node (ref "R4") (pin "2") (pinfunction "2_2") (pintype "passive"))
      (node (ref "U4") (pin "3") (pinfunction "SEL_3") (pintype "passive"))
    )
    (net (code "28") (name "Net-(U4-VDD)") (class "Default")
      (node (ref "C4") (pin "1") (pinfunction "1_1") (pintype "passive"))
      (node (ref "C5") (pin "2") (pinfunction "2_2") (pintype "passive"))
      (node (ref "CE4") (pin "1") (pinfunction "1_1") (pintype "passive"))
      (node (ref "CE5") (pin "2") (pinfunction "2_2") (pintype "passive"))
      (node (ref "Q5") (pin "1") (pinfunction "S_1") (pintype "passive"))
      (node (ref "Q5") (pin "2") (pinfunction "S_2") (pintype "passive"))
      (node (ref "Q5") (pin "3") (pinfunction "S_3") (pintype "passive"))
      (node (ref "R10") (pin "1") (pinfunction "1_1") (pintype "passive"))
      (node (ref "R14") (pin "2") (pinfunction "2_2") (pintype "passive"))
      (node (ref "R19") (pin "2") (pinfunction "2_2") (pintype "passive"))
      (node (ref "R4") (pin "1") (pinfunction "1_1") (pintype "passive"))
      (node (ref "U4") (pin "1") (pinfunction "VDD_1") (pintype "passive"))
      (node (ref "U5") (pin "2") (pinfunction "GND_2") (pintype "passive"))
    )
    (net (code "29") (name "Net-(U5-SEL)") (class "Default")
      (node (ref "R5") (pin "2") (pinfunction "2_2") (pintype "passive"))
      (node (ref "U5") (pin "3") (pinfunction "SEL_3") (pintype "passive"))
    )
    (net (code "30") (name "Net-(U6-SEL)") (class "Default")
      (node (ref "R21") (pin "2") (pinfunction "2_2") (pintype "passive"))
      (node (ref "U6") (pin "3") (pinfunction "SEL_3") (pintype "passive"))
    )
    (net (code "31") (name "Net-(U6-VDD)") (class "Default")
      (node (ref "C6") (pin "1") (pinfunction "1_1") (pintype "passive"))
      (node (ref "C7") (pin "2") (pinfunction "2_2") (pintype "passive"))
      (node (ref "CE6") (pin "1") (pinfunction "1_1") (pintype "passive"))
      (node (ref "CE7") (pin "2") (pinfunction "2_2") (pintype "passive"))
      (node (ref "Q7") (pin "1") (pinfunction "S_1") (pintype "passive"))
      (node (ref "Q7") (pin "2") (pinfunction "S_2") (pintype "passive"))
      (node (ref "Q7") (pin "3") (pinfunction "S_3") (pintype "passive"))
      (node (ref "R21") (pin "1") (pinfunction "1_1") (pintype "passive"))
      (node (ref "R26") (pin "1") (pinfunction "1_1") (pintype "passive"))
      (node (ref "R29") (pin "2") (pinfunction "2_2") (pintype "passive"))
      (node (ref "R33") (pin "2") (pinfunction "2_2") (pintype "passive"))
      (node (ref "U6") (pin "1") (pinfunction "VDD_1") (pintype "passive"))
      (node (ref "U7") (pin "2") (pinfunction "GND_2") (pintype "passive"))
    )
    (net (code "32") (name "Net-(U7-SEL)") (class "Default")
      (node (ref "R22") (pin "2") (pinfunction "2_2") (pintype "passive"))
      (node (ref "U7") (pin "3") (pinfunction "SEL_3") (pintype "passive"))
    )
    (net (code "33") (name "Net-(U7-VDD)") (class "Default")
      (node (ref "C7") (pin "1") (pinfunction "1_1") (pintype "passive"))
      (node (ref "C8") (pin "2") (pinfunction "2_2") (pintype "passive"))
      (node (ref "CE7") (pin "1") (pinfunction "1_1") (pintype "passive"))
      (node (ref "CE8") (pin "2") (pinfunction "2_2") (pintype "passive"))
      (node (ref "Q8") (pin "1") (pinfunction "S_1") (pintype "passive"))
      (node (ref "Q8") (pin "2") (pinfunction "S_2") (pintype "passive"))
      (node (ref "Q8") (pin "3") (pinfunction "S_3") (pintype "passive"))
      (node (ref "R22") (pin "1") (pinfunction "1_1") (pintype "passive"))
      (node (ref "R27") (pin "1") (pinfunction "1_1") (pintype "passive"))
      (node (ref "R30") (pin "2") (pinfunction "2_2") (pintype "passive"))
      (node (ref "R34") (pin "2") (pinfunction "2_2") (pintype "passive"))
      (node (ref "U7") (pin "1") (pinfunction "VDD_1") (pintype "passive"))
      (node (ref "U8") (pin "2") (pinfunction "GND_2") (pintype "passive"))
    )
    (net (code "34") (name "Net-(U8-SEL)") (class "Default")
      (node (ref "R23") (pin "2") (pinfunction "2_2") (pintype "passive"))
      (node (ref "U8") (pin "3") (pinfunction "SEL_3") (pintype "passive"))
    )
    (net (code "35") (name "Net-(U8-VDD)") (class "Default")
      (node (ref "C8") (pin "1") (pinfunction "1_1") (pintype "passive"))
      (node (ref "C9") (pin "2") (pinfunction "2_2") (pintype "passive"))
      (node (ref "CE8") (pin "1") (pinfunction "1_1") (pintype "passive"))
      (node (ref "CE9") (pin "2") (pinfunction "2_2") (pintype "passive"))
      (node (ref "Q9") (pin "1") (pinfunction "S_1") (pintype "passive"))
      (node (ref "Q9") (pin "2") (pinfunction "S_2") (pintype "passive"))
      (node (ref "Q9") (pin "3") (pinfunction "S_3") (pintype "passive"))
      (node (ref "R23") (pin "1") (pinfunction "1_1") (pintype "passive"))
      (node (ref "R28") (pin "1") (pinfunction "1_1") (pintype "passive"))
      (node (ref "R31") (pin "2") (pinfunction "2_2") (pintype "passive"))
      (node (ref "R35") (pin "2") (pinfunction "2_2") (pintype "passive"))
      (node (ref "U8") (pin "1") (pinfunction "VDD_1") (pintype "passive"))
      (node (ref "U9") (pin "2") (pinfunction "GND_2") (pintype "passive"))
    )
    (net (code "36") (name "Net-(U9-SEL)") (class "Default")
      (node (ref "R24") (pin "2") (pinfunction "2_2") (pintype "passive"))
      (node (ref "U9") (pin "3") (pinfunction "SEL_3") (pintype "passive"))
    )
    (net (code "37") (name "V_Capin") (class "Default")
      (node (ref "C9") (pin "1") (pinfunction "1_1") (pintype "passive"))
      (node (ref "CE9") (pin "1") (pinfunction "1_1") (pintype "passive"))
      (node (ref "CapA") (pin "1") (pinfunction "1_1") (pintype "passive"))
      (node (ref "CapB") (pin "1") (pinfunction "1_1") (pintype "passive"))
      (node (ref "CapC") (pin "1") (pinfunction "1_1") (pintype "passive"))
      (node (ref "R24") (pin "1") (pinfunction "1_1") (pintype "passive"))
      (node (ref "R32") (pin "2") (pinfunction "2_2") (pintype "passive"))
      (node (ref "R36") (pin "2") (pinfunction "2_2") (pintype "passive"))
      (node (ref "U9") (pin "1") (pinfunction "VDD_1") (pintype "passive"))
    )
    (net (code "38") (name "unconnected-(U1-LED-Pad4)") (class "Default")
      (node (ref "U1") (pin "4") (pinfunction "LED_4") (pintype "passive+no_connect"))
    )
    (net (code "39") (name "unconnected-(U2-LED-Pad4)") (class "Default")
      (node (ref "U2") (pin "4") (pinfunction "LED_4") (pintype "passive+no_connect"))
    )
    (net (code "40") (name "unconnected-(U3-LED-Pad4)") (class "Default")
      (node (ref "U3") (pin "4") (pinfunction "LED_4") (pintype "passive+no_connect"))
    )
    (net (code "41") (name "unconnected-(U4-LED-Pad4)") (class "Default")
      (node (ref "U4") (pin "4") (pinfunction "LED_4") (pintype "passive+no_connect"))
    )
    (net (code "42") (name "unconnected-(U5-LED-Pad4)") (class "Default")
      (node (ref "U5") (pin "4") (pinfunction "LED_4") (pintype "passive+no_connect"))
    )
    (net (code "43") (name "unconnected-(U6-LED-Pad4)") (class "Default")
      (node (ref "U6") (pin "4") (pinfunction "LED_4") (pintype "passive+no_connect"))
    )
    (net (code "44") (name "unconnected-(U7-LED-Pad4)") (class "Default")
      (node (ref "U7") (pin "4") (pinfunction "LED_4") (pintype "passive+no_connect"))
    )
    (net (code "45") (name "unconnected-(U8-LED-Pad4)") (class "Default")
      (node (ref "U8") (pin "4") (pinfunction "LED_4") (pintype "passive+no_connect"))
    )
    (net (code "46") (name "unconnected-(U9-LED-Pad4)") (class "Default")
      (node (ref "U9") (pin "4") (pinfunction "LED_4") (pintype "passive+no_connect"))
    )
  )
)
